# 328p__ver1.net
KiCad netlist of a schematic drawn in EAGLE
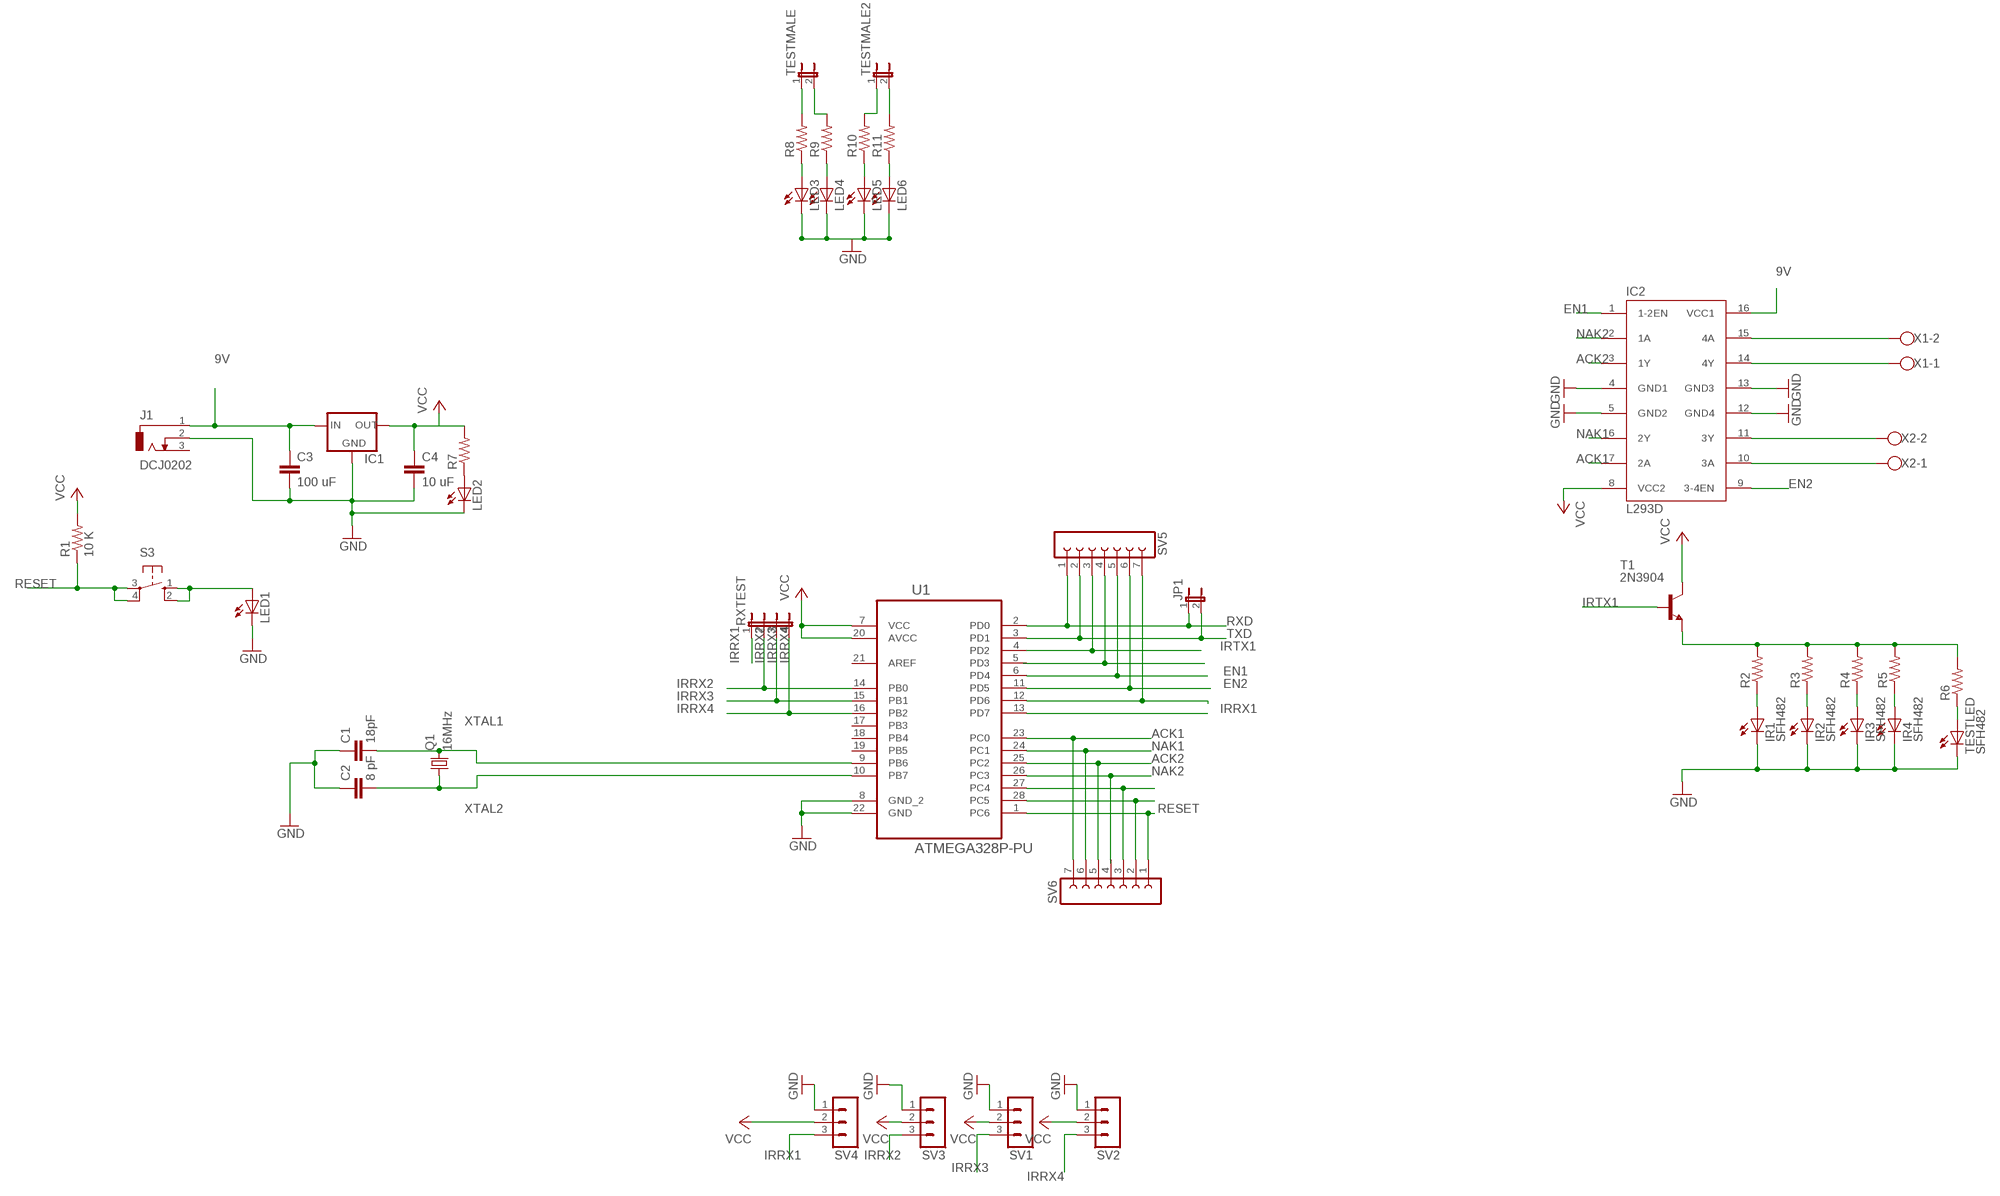
[diagram p0: schematic, sheet 1]

(export (version "E")
  (design (tool "Eeschema 10.0.6"))
  (components
    (comp (ref "C1")
      (value "18pF")
      (footprint "eagle-import:C2.5-3")
      (libsource (lib "eagle-import") (part "C2,5-3"))
    )
    (comp (ref "C2")
      (value "8 pF")
      (footprint "eagle-import:C2.5-3")
      (libsource (lib "eagle-import") (part "C2,5-3"))
    )
    (comp (ref "C3")
      (value "100 uF")
      (footprint "eagle-import:C2.5-3")
      (libsource (lib "eagle-import") (part "C2,5-3"))
    )
    (comp (ref "C4")
      (value "10 uF")
      (footprint "eagle-import:C2.5-3")
      (libsource (lib "eagle-import") (part "C2,5-3"))
    )
    (comp (ref "IC1")
      (value "78XXS")
      (footprint "eagle-import:78XXS")
      (libsource (lib "eagle-import") (part "78XXS"))
    )
    (comp (ref "IC2")
      (value "L293D")
      (footprint "eagle-import:DIL16")
      (libsource (lib "eagle-import") (part "L293D"))
    )
    (comp (ref "IR1")
      (value "SFH482")
      (footprint "eagle-import:SFH482")
      (libsource (lib "eagle-import") (part "SFH482"))
    )
    (comp (ref "IR2")
      (value "SFH482")
      (footprint "eagle-import:SFH482")
      (libsource (lib "eagle-import") (part "SFH482"))
    )
    (comp (ref "IR3")
      (value "SFH482")
      (footprint "eagle-import:SFH482")
      (libsource (lib "eagle-import") (part "SFH482"))
    )
    (comp (ref "IR4")
      (value "SFH482")
      (footprint "eagle-import:SFH482")
      (libsource (lib "eagle-import") (part "SFH482"))
    )
    (comp (ref "J1")
      (value "DCJ0202")
      (footprint "eagle-import:DCJ0202")
      (libsource (lib "eagle-import") (part "DCJ0202"))
    )
    (comp (ref "JP1")
      (value "JP1E")
      (footprint "eagle-import:JP1")
      (libsource (lib "eagle-import") (part "JP1E"))
    )
    (comp (ref "LED1")
      (value "LED3MM")
      (footprint "eagle-import:LED3MM")
      (libsource (lib "eagle-import") (part "LED3MM"))
    )
    (comp (ref "LED2")
      (value "LED3MM")
      (footprint "eagle-import:LED3MM")
      (libsource (lib "eagle-import") (part "LED3MM"))
    )
    (comp (ref "LED3")
      (value "LED3MM")
      (footprint "eagle-import:LED3MM")
      (libsource (lib "eagle-import") (part "LED3MM"))
    )
    (comp (ref "LED4")
      (value "LED3MM")
      (footprint "eagle-import:LED3MM")
      (libsource (lib "eagle-import") (part "LED3MM"))
    )
    (comp (ref "LED5")
      (value "LED3MM")
      (footprint "eagle-import:LED3MM")
      (libsource (lib "eagle-import") (part "LED3MM"))
    )
    (comp (ref "LED6")
      (value "LED3MM")
      (footprint "eagle-import:LED3MM")
      (libsource (lib "eagle-import") (part "LED3MM"))
    )
    (comp (ref "Q1")
      (value "16MHz")
      (footprint "eagle-import:HC49_S")
      (libsource (lib "eagle-import") (part "CRYSTALHC49S"))
    )
    (comp (ref "R1")
      (value "10 K")
      (footprint "eagle-import:0207_12")
      (libsource (lib "eagle-import") (part "R-US_0207/12"))
    )
    (comp (ref "R2")
      (value "R-US_0204/7")
      (footprint "eagle-import:0204_7")
      (libsource (lib "eagle-import") (part "R-US_0204/7"))
    )
    (comp (ref "R3")
      (value "R-US_0204/7")
      (footprint "eagle-import:0204_7")
      (libsource (lib "eagle-import") (part "R-US_0204/7"))
    )
    (comp (ref "R4")
      (value "R-US_0204/7")
      (footprint "eagle-import:0204_7")
      (libsource (lib "eagle-import") (part "R-US_0204/7"))
    )
    (comp (ref "R5")
      (value "R-US_0204/7")
      (footprint "eagle-import:0204_7")
      (libsource (lib "eagle-import") (part "R-US_0204/7"))
    )
    (comp (ref "R6")
      (value "R-US_0204/7")
      (footprint "eagle-import:0204_7")
      (libsource (lib "eagle-import") (part "R-US_0204/7"))
    )
    (comp (ref "R7")
      (value "R-US_0204/7")
      (footprint "eagle-import:0204_7")
      (libsource (lib "eagle-import") (part "R-US_0204/7"))
    )
    (comp (ref "R8")
      (value "R-US_0204/7")
      (footprint "eagle-import:0204_7")
      (libsource (lib "eagle-import") (part "R-US_0204/7"))
    )
    (comp (ref "R9")
      (value "R-US_0204/7")
      (footprint "eagle-import:0204_7")
      (libsource (lib "eagle-import") (part "R-US_0204/7"))
    )
    (comp (ref "R10")
      (value "R-US_0204/7")
      (footprint "eagle-import:0204_7")
      (libsource (lib "eagle-import") (part "R-US_0204/7"))
    )
    (comp (ref "R11")
      (value "R-US_0204/7")
      (footprint "eagle-import:0204_7")
      (libsource (lib "eagle-import") (part "R-US_0204/7"))
    )
    (comp (ref "RXTEST")
      (value "JP4E")
      (footprint "eagle-import:JP4")
      (libsource (lib "eagle-import") (part "JP4E"))
    )
    (comp (ref "S3")
      (value "10-XX")
      (footprint "eagle-import:B3F-10XX")
      (fields (field (name "MPN") "B3F-1000"))
      (libsource (lib "eagle-import") (part "10-XX"))
    )
    (comp (ref "SV1")
      (value "MA03-1")
      (footprint "eagle-import:MA03-1")
      (libsource (lib "eagle-import") (part "MA03-1"))
    )
    (comp (ref "SV2")
      (value "MA03-1")
      (footprint "eagle-import:MA03-1")
      (libsource (lib "eagle-import") (part "MA03-1"))
    )
    (comp (ref "SV3")
      (value "MA03-1")
      (footprint "eagle-import:MA03-1")
      (libsource (lib "eagle-import") (part "MA03-1"))
    )
    (comp (ref "SV4")
      (value "MA03-1")
      (footprint "eagle-import:MA03-1")
      (libsource (lib "eagle-import") (part "MA03-1"))
    )
    (comp (ref "SV5")
      (value "FE07-1")
      (footprint "eagle-import:FE07")
      (libsource (lib "eagle-import") (part "FE07-1"))
    )
    (comp (ref "SV6")
      (value "FE07-1")
      (footprint "eagle-import:FE07")
      (libsource (lib "eagle-import") (part "FE07-1"))
    )
    (comp (ref "T1")
      (value "2N3904")
      (footprint "eagle-import:TO92")
      (libsource (lib "eagle-import") (part "2N3904"))
    )
    (comp (ref "TESTLED")
      (value "SFH482")
      (footprint "eagle-import:SFH482")
      (libsource (lib "eagle-import") (part "SFH482"))
    )
    (comp (ref "TESTMALE")
      (value "JP1E")
      (footprint "eagle-import:JP1")
      (libsource (lib "eagle-import") (part "JP1E"))
    )
    (comp (ref "TESTMALE2")
      (value "JP1E")
      (footprint "eagle-import:JP1")
      (libsource (lib "eagle-import") (part "JP1E"))
    )
    (comp (ref "U1")
      (value "ATMEGA328P-PU")
      (footprint "eagle-import:DIP254P762X457-28")
      (libsource (lib "eagle-import") (part "ATMEGA328P-PU"))
    )
    (comp (ref "X1")
      (value "W237-102")
      (footprint "eagle-import:W237-102")
      (fields (field (name "MPN") "237-102"))
      (libsource (lib "eagle-import") (part "W237-102"))
    )
    (comp (ref "X2")
      (value "W237-102")
      (footprint "eagle-import:W237-102")
      (fields (field (name "MPN") "237-102"))
      (libsource (lib "eagle-import") (part "W237-102"))
    )
  )
  (nets
    (net (code "1") (name "/9V") (class "Default")
      (node (ref "C3") (pin "1") (pinfunction "1_1") (pintype "passive"))
      (node (ref "IC1") (pin "IN") (pinfunction "IN_IN") (pintype "input"))
      (node (ref "IC2") (pin "16") (pinfunction "VCC1_16") (pintype "power_in"))
      (node (ref "J1") (pin "1") (pinfunction "1_1") (pintype "passive"))
    )
    (net (code "2") (name "/ACK1") (class "Default")
      (node (ref "IC2") (pin "7") (pinfunction "2A_7") (pintype "input"))
      (node (ref "SV6") (pin "7") (pinfunction "7_7") (pintype "passive"))
      (node (ref "U1") (pin "23") (pinfunction "PC0_23") (pintype "bidirectional"))
    )
    (net (code "3") (name "/ACK2") (class "Default")
      (node (ref "IC2") (pin "3") (pinfunction "1Y_3") (pintype "output"))
      (node (ref "SV6") (pin "5") (pinfunction "5_5") (pintype "passive"))
      (node (ref "U1") (pin "25") (pinfunction "PC2_25") (pintype "bidirectional"))
    )
    (net (code "4") (name "/EN1") (class "Default")
      (node (ref "IC2") (pin "1") (pinfunction "1-2EN_1") (pintype "input"))
      (node (ref "SV5") (pin "5") (pinfunction "5_5") (pintype "passive"))
      (node (ref "U1") (pin "6") (pinfunction "PD4_6") (pintype "bidirectional"))
    )
    (net (code "5") (name "/EN2") (class "Default")
      (node (ref "IC2") (pin "9") (pinfunction "3-4EN_9") (pintype "input"))
      (node (ref "SV5") (pin "6") (pinfunction "6_6") (pintype "passive"))
      (node (ref "U1") (pin "11") (pinfunction "PD5_11") (pintype "bidirectional"))
    )
    (net (code "6") (name "/IRRX1") (class "Default")
      (node (ref "RXTEST") (pin "1") (pinfunction "1_1") (pintype "passive"))
      (node (ref "SV4") (pin "3") (pinfunction "3_3") (pintype "passive"))
      (node (ref "U1") (pin "13") (pinfunction "PD7_13") (pintype "bidirectional"))
    )
    (net (code "7") (name "/IRRX2") (class "Default")
      (node (ref "RXTEST") (pin "2") (pinfunction "2_2") (pintype "passive"))
      (node (ref "SV3") (pin "3") (pinfunction "3_3") (pintype "passive"))
      (node (ref "U1") (pin "14") (pinfunction "PB0_14") (pintype "bidirectional"))
    )
    (net (code "8") (name "/IRRX3") (class "Default")
      (node (ref "RXTEST") (pin "3") (pinfunction "3_3") (pintype "passive"))
      (node (ref "SV1") (pin "3") (pinfunction "3_3") (pintype "passive"))
      (node (ref "U1") (pin "15") (pinfunction "PB1_15") (pintype "bidirectional"))
    )
    (net (code "9") (name "/IRRX4") (class "Default")
      (node (ref "RXTEST") (pin "4") (pinfunction "4_4") (pintype "passive"))
      (node (ref "SV2") (pin "3") (pinfunction "3_3") (pintype "passive"))
      (node (ref "U1") (pin "16") (pinfunction "PB2_16") (pintype "bidirectional"))
    )
    (net (code "10") (name "/IRTX1") (class "Default")
      (node (ref "SV5") (pin "3") (pinfunction "3_3") (pintype "passive"))
      (node (ref "T1") (pin "2") (pinfunction "B_2") (pintype "passive"))
      (node (ref "U1") (pin "4") (pinfunction "PD2_4") (pintype "bidirectional"))
    )
    (net (code "11") (name "/NAK1") (class "Default")
      (node (ref "IC2") (pin "6") (pinfunction "2Y_6") (pintype "output"))
      (node (ref "SV6") (pin "6") (pinfunction "6_6") (pintype "passive"))
      (node (ref "U1") (pin "24") (pinfunction "PC1_24") (pintype "bidirectional"))
    )
    (net (code "12") (name "/NAK2") (class "Default")
      (node (ref "IC2") (pin "2") (pinfunction "1A_2") (pintype "input"))
      (node (ref "U1") (pin "26") (pinfunction "PC3_26") (pintype "bidirectional"))
    )
    (net (code "13") (name "/RESET") (class "Default")
      (node (ref "R1") (pin "1") (pinfunction "1_1") (pintype "passive"))
      (node (ref "S3") (pin "3") (pinfunction "P_3") (pintype "passive"))
      (node (ref "S3") (pin "4") (pinfunction "P1_4") (pintype "passive"))
      (node (ref "SV6") (pin "1") (pinfunction "1_1") (pintype "passive"))
      (node (ref "U1") (pin "1") (pinfunction "PC6_1") (pintype "bidirectional"))
    )
    (net (code "14") (name "/RXD") (class "Default")
      (node (ref "JP1") (pin "1") (pinfunction "1_1") (pintype "passive"))
      (node (ref "SV5") (pin "1") (pinfunction "1_1") (pintype "passive"))
      (node (ref "U1") (pin "2") (pinfunction "PD0_2") (pintype "bidirectional"))
    )
    (net (code "15") (name "/TXD") (class "Default")
      (node (ref "JP1") (pin "2") (pinfunction "2_2") (pintype "passive"))
      (node (ref "SV5") (pin "2") (pinfunction "2_2") (pintype "passive"))
      (node (ref "U1") (pin "3") (pinfunction "PD1_3") (pintype "bidirectional"))
    )
    (net (code "16") (name "/XTAL1") (class "Default")
      (node (ref "C1") (pin "2") (pinfunction "2_2") (pintype "passive"))
      (node (ref "Q1") (pin "2") (pinfunction "2_2") (pintype "passive"))
      (node (ref "U1") (pin "9") (pinfunction "PB6_9") (pintype "bidirectional"))
    )
    (net (code "17") (name "/XTAL2") (class "Default")
      (node (ref "C2") (pin "2") (pinfunction "2_2") (pintype "passive"))
      (node (ref "Q1") (pin "1") (pinfunction "1_1") (pintype "passive"))
      (node (ref "U1") (pin "10") (pinfunction "PB7_10") (pintype "bidirectional"))
    )
    (net (code "18") (name "GND") (class "Default")
      (node (ref "C1") (pin "1") (pinfunction "1_1") (pintype "passive"))
      (node (ref "C2") (pin "1") (pinfunction "1_1") (pintype "passive"))
      (node (ref "C3") (pin "2") (pinfunction "2_2") (pintype "passive"))
      (node (ref "C4") (pin "2") (pinfunction "2_2") (pintype "passive"))
      (node (ref "IC1") (pin "GND") (pinfunction "GND_GND") (pintype "input"))
      (node (ref "IC2") (pin "12") (pinfunction "GND4_12") (pintype "power_in"))
      (node (ref "IC2") (pin "13") (pinfunction "GND3_13") (pintype "power_in"))
      (node (ref "IC2") (pin "4") (pinfunction "GND1_4") (pintype "power_in"))
      (node (ref "IC2") (pin "5") (pinfunction "GND2_5") (pintype "power_in"))
      (node (ref "IR1") (pin "K") (pinfunction "C_K") (pintype "passive"))
      (node (ref "IR2") (pin "K") (pinfunction "C_K") (pintype "passive"))
      (node (ref "IR3") (pin "K") (pinfunction "C_K") (pintype "passive"))
      (node (ref "IR4") (pin "K") (pinfunction "C_K") (pintype "passive"))
      (node (ref "J1") (pin "2") (pinfunction "2_2") (pintype "passive"))
      (node (ref "LED1") (pin "K") (pinfunction "C_K") (pintype "passive"))
      (node (ref "LED2") (pin "K") (pinfunction "C_K") (pintype "passive"))
      (node (ref "LED3") (pin "K") (pinfunction "C_K") (pintype "passive"))
      (node (ref "LED4") (pin "K") (pinfunction "C_K") (pintype "passive"))
      (node (ref "LED5") (pin "K") (pinfunction "C_K") (pintype "passive"))
      (node (ref "LED6") (pin "K") (pinfunction "C_K") (pintype "passive"))
      (node (ref "SV1") (pin "1") (pinfunction "1_1") (pintype "passive"))
      (node (ref "SV2") (pin "1") (pinfunction "1_1") (pintype "passive"))
      (node (ref "SV3") (pin "1") (pinfunction "1_1") (pintype "passive"))
      (node (ref "SV4") (pin "1") (pinfunction "1_1") (pintype "passive"))
      (node (ref "TESTLED") (pin "K") (pinfunction "C_K") (pintype "passive"))
      (node (ref "U1") (pin "22") (pinfunction "GND_22") (pintype "passive"))
      (node (ref "U1") (pin "8") (pinfunction "GND_2_8") (pintype "passive"))
    )
    (net (code "19") (name "Net-(IC2-3A)") (class "Default")
      (node (ref "IC2") (pin "10") (pinfunction "3A_10") (pintype "input"))
      (node (ref "X2") (pin "1") (pinfunction "KL_1") (pintype "passive"))
    )
    (net (code "20") (name "Net-(IC2-3Y)") (class "Default")
      (node (ref "IC2") (pin "11") (pinfunction "3Y_11") (pintype "output"))
      (node (ref "X2") (pin "2") (pinfunction "KL_2") (pintype "passive"))
    )
    (net (code "21") (name "Net-(IC2-4A)") (class "Default")
      (node (ref "IC2") (pin "15") (pinfunction "4A_15") (pintype "input"))
      (node (ref "X1") (pin "2") (pinfunction "KL_2") (pintype "passive"))
    )
    (net (code "22") (name "Net-(IC2-4Y)") (class "Default")
      (node (ref "IC2") (pin "14") (pinfunction "4Y_14") (pintype "output"))
      (node (ref "X1") (pin "1") (pinfunction "KL_1") (pintype "passive"))
    )
    (net (code "23") (name "Net-(IR1-PadA)") (class "Default")
      (node (ref "IR1") (pin "A") (pinfunction "A_A") (pintype "passive"))
      (node (ref "R2") (pin "1") (pinfunction "1_1") (pintype "passive"))
    )
    (net (code "24") (name "Net-(IR2-PadA)") (class "Default")
      (node (ref "IR2") (pin "A") (pinfunction "A_A") (pintype "passive"))
      (node (ref "R3") (pin "1") (pinfunction "1_1") (pintype "passive"))
    )
    (net (code "25") (name "Net-(IR3-PadA)") (class "Default")
      (node (ref "IR3") (pin "A") (pinfunction "A_A") (pintype "passive"))
      (node (ref "R4") (pin "1") (pinfunction "1_1") (pintype "passive"))
    )
    (net (code "26") (name "Net-(IR4-PadA)") (class "Default")
      (node (ref "IR4") (pin "A") (pinfunction "A_A") (pintype "passive"))
      (node (ref "R5") (pin "1") (pinfunction "1_1") (pintype "passive"))
    )
    (net (code "27") (name "Net-(LED2-PadA)") (class "Default")
      (node (ref "LED2") (pin "A") (pinfunction "A_A") (pintype "passive"))
      (node (ref "R7") (pin "1") (pinfunction "1_1") (pintype "passive"))
    )
    (net (code "28") (name "Net-(LED3-PadA)") (class "Default")
      (node (ref "LED3") (pin "A") (pinfunction "A_A") (pintype "passive"))
      (node (ref "R8") (pin "1") (pinfunction "1_1") (pintype "passive"))
    )
    (net (code "29") (name "Net-(LED4-PadA)") (class "Default")
      (node (ref "LED4") (pin "A") (pinfunction "A_A") (pintype "passive"))
      (node (ref "R9") (pin "1") (pinfunction "1_1") (pintype "passive"))
    )
    (net (code "30") (name "Net-(LED5-PadA)") (class "Default")
      (node (ref "LED5") (pin "A") (pinfunction "A_A") (pintype "passive"))
      (node (ref "R10") (pin "1") (pinfunction "1_1") (pintype "passive"))
    )
    (net (code "31") (name "Net-(LED6-PadA)") (class "Default")
      (node (ref "LED6") (pin "A") (pinfunction "A_A") (pintype "passive"))
      (node (ref "R11") (pin "1") (pinfunction "1_1") (pintype "passive"))
    )
    (net (code "32") (name "Net-(R6-Pad1)") (class "Default")
      (node (ref "R6") (pin "1") (pinfunction "1_1") (pintype "passive"))
      (node (ref "TESTLED") (pin "A") (pinfunction "A_A") (pintype "passive"))
    )
    (net (code "33") (name "Net-(R8-Pad2)") (class "Default")
      (node (ref "R8") (pin "2") (pinfunction "2_2") (pintype "passive"))
      (node (ref "TESTMALE") (pin "1") (pinfunction "1_1") (pintype "passive"))
    )
    (net (code "34") (name "Net-(R9-Pad2)") (class "Default")
      (node (ref "R9") (pin "2") (pinfunction "2_2") (pintype "passive"))
      (node (ref "TESTMALE") (pin "2") (pinfunction "2_2") (pintype "passive"))
    )
    (net (code "35") (name "Net-(R10-Pad2)") (class "Default")
      (node (ref "R10") (pin "2") (pinfunction "2_2") (pintype "passive"))
      (node (ref "TESTMALE2") (pin "1") (pinfunction "1_1") (pintype "passive"))
    )
    (net (code "36") (name "Net-(R11-Pad2)") (class "Default")
      (node (ref "R11") (pin "2") (pinfunction "2_2") (pintype "passive"))
      (node (ref "TESTMALE2") (pin "2") (pinfunction "2_2") (pintype "passive"))
    )
    (net (code "37") (name "Net-(S3-S)") (class "Default")
      (node (ref "LED1") (pin "A") (pinfunction "A_A") (pintype "passive"))
      (node (ref "S3") (pin "1") (pinfunction "S_1") (pintype "passive"))
      (node (ref "S3") (pin "2") (pinfunction "S1_2") (pintype "passive"))
    )
    (net (code "38") (name "Net-(T1-E)") (class "Default")
      (node (ref "R2") (pin "2") (pinfunction "2_2") (pintype "passive"))
      (node (ref "R3") (pin "2") (pinfunction "2_2") (pintype "passive"))
      (node (ref "R4") (pin "2") (pinfunction "2_2") (pintype "passive"))
      (node (ref "R5") (pin "2") (pinfunction "2_2") (pintype "passive"))
      (node (ref "R6") (pin "2") (pinfunction "2_2") (pintype "passive"))
      (node (ref "T1") (pin "3") (pinfunction "E_3") (pintype "passive"))
    )
    (net (code "39") (name "Net-(U1-PC4)") (class "Default")
      (node (ref "SV6") (pin "3") (pinfunction "3_3") (pintype "passive"))
      (node (ref "U1") (pin "27") (pinfunction "PC4_27") (pintype "bidirectional"))
    )
    (net (code "40") (name "Net-(U1-PC5)") (class "Default")
      (node (ref "SV6") (pin "2") (pinfunction "2_2") (pintype "passive"))
      (node (ref "U1") (pin "28") (pinfunction "PC5_28") (pintype "bidirectional"))
    )
    (net (code "41") (name "Net-(U1-PD6)") (class "Default")
      (node (ref "SV5") (pin "7") (pinfunction "7_7") (pintype "passive"))
      (node (ref "U1") (pin "12") (pinfunction "PD6_12") (pintype "bidirectional"))
    )
    (net (code "42") (name "VCC") (class "Default")
      (node (ref "C4") (pin "1") (pinfunction "1_1") (pintype "passive"))
      (node (ref "IC1") (pin "OUT") (pinfunction "OUT_OUT") (pintype "passive"))
      (node (ref "IC2") (pin "8") (pinfunction "VCC2_8") (pintype "power_in"))
      (node (ref "R1") (pin "2") (pinfunction "2_2") (pintype "passive"))
      (node (ref "R7") (pin "2") (pinfunction "2_2") (pintype "passive"))
      (node (ref "SV1") (pin "2") (pinfunction "2_2") (pintype "passive"))
      (node (ref "SV2") (pin "2") (pinfunction "2_2") (pintype "passive"))
      (node (ref "SV3") (pin "2") (pinfunction "2_2") (pintype "passive"))
      (node (ref "SV4") (pin "2") (pinfunction "2_2") (pintype "passive"))
      (node (ref "T1") (pin "1") (pinfunction "C_1") (pintype "passive"))
      (node (ref "U1") (pin "20") (pinfunction "AVCC_20") (pintype "power_in"))
      (node (ref "U1") (pin "7") (pinfunction "VCC_7") (pintype "power_in"))
    )
    (net (code "43") (name "unconnected-(J1-Pad3)") (class "Default")
      (node (ref "J1") (pin "3") (pinfunction "3_3") (pintype "passive"))
    )
    (net (code "44") (name "unconnected-(SV5-Pad4)") (class "Default")
      (node (ref "SV5") (pin "4") (pinfunction "4_4") (pintype "passive"))
    )
    (net (code "45") (name "unconnected-(SV6-Pad4)") (class "Default")
      (node (ref "SV6") (pin "4") (pinfunction "4_4") (pintype "passive"))
    )
    (net (code "46") (name "unconnected-(U1-AREF-Pad21)") (class "Default")
      (node (ref "U1") (pin "21") (pinfunction "AREF_21") (pintype "input"))
    )
    (net (code "47") (name "unconnected-(U1-PB3-Pad17)") (class "Default")
      (node (ref "U1") (pin "17") (pinfunction "PB3_17") (pintype "bidirectional"))
    )
    (net (code "48") (name "unconnected-(U1-PB4-Pad18)") (class "Default")
      (node (ref "U1") (pin "18") (pinfunction "PB4_18") (pintype "bidirectional"))
    )
    (net (code "49") (name "unconnected-(U1-PB5-Pad19)") (class "Default")
      (node (ref "U1") (pin "19") (pinfunction "PB5_19") (pintype "bidirectional"))
    )
    (net (code "50") (name "unconnected-(U1-PD3-Pad5)") (class "Default")
      (node (ref "U1") (pin "5") (pinfunction "PD3_5") (pintype "bidirectional"))
    )
  )
)
